# Qwiic_KX13X.net
KiCad netlist of a schematic drawn in EAGLE
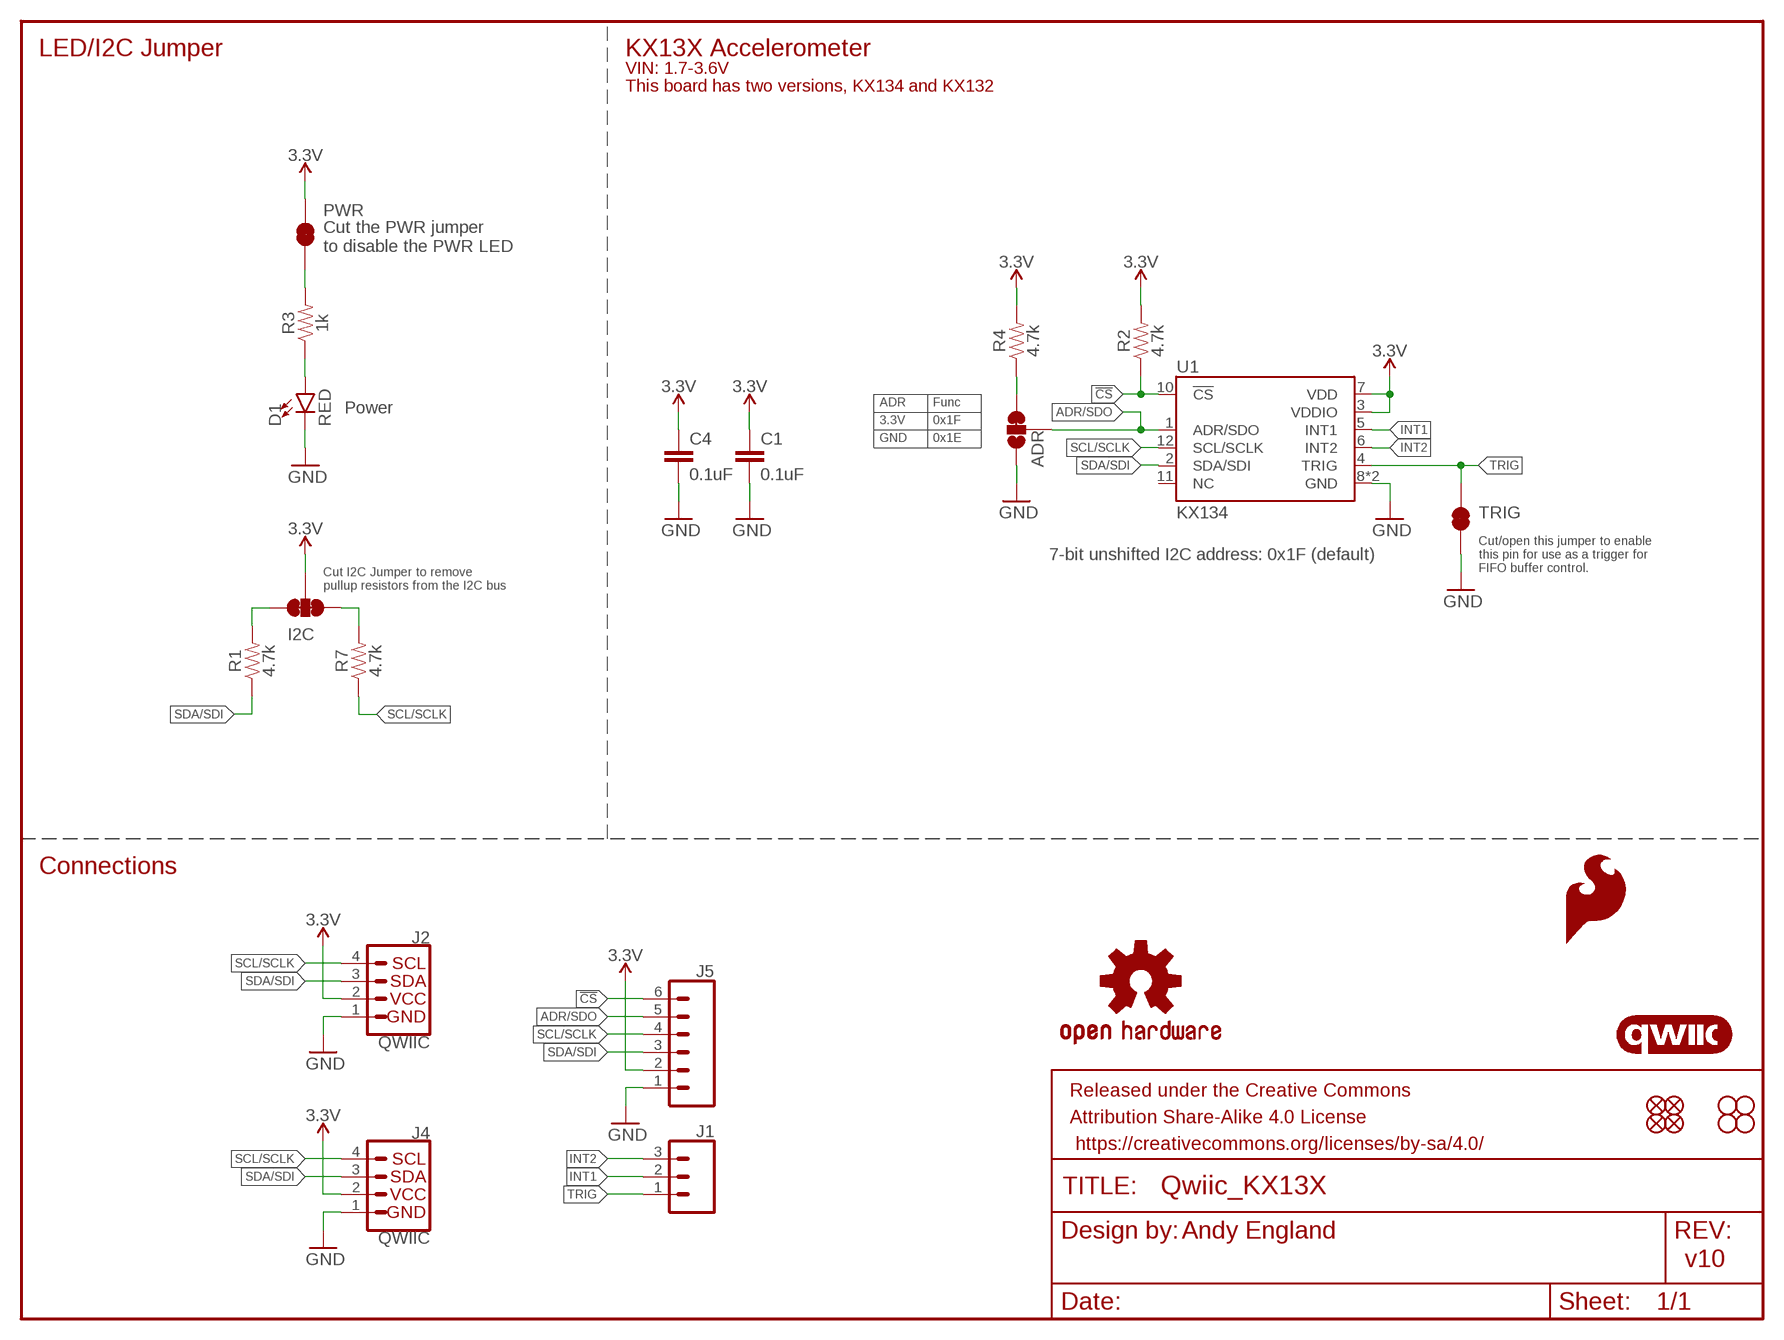
[diagram p0: schematic, sheet 1]

(export (version "E")
  (design (tool "Eeschema 10.0.6"))
  (components
    (comp (ref "ADR")
      (value "JUMPER-SMT_3_1-NC_TRACE_SILK")
      (footprint "eagle-import:SMT-JUMPER_3_1-NC_TRACE_SILK")
      (libsource (lib "eagle-import") (part "JUMPER-SMT_3_1-NC_TRACE_SILK"))
    )
    (comp (ref "C1")
      (value "0.1uF")
      (footprint "eagle-import:0603")
      (libsource (lib "eagle-import") (part "0.1UF-0603-25V-(+80/-20%)"))
    )
    (comp (ref "C4")
      (value "0.1uF")
      (footprint "eagle-import:0603")
      (libsource (lib "eagle-import") (part "0.1UF-0603-25V-(+80/-20%)"))
    )
    (comp (ref "D1")
      (value "RED")
      (footprint "eagle-import:LED-0603")
      (libsource (lib "eagle-import") (part "LED-RED0603"))
    )
    (comp (ref "FRAME1")
      (value "FRAME-LETTER")
      (footprint "eagle-import:CREATIVE_COMMONS")
      (libsource (lib "eagle-import") (part "FRAME-LETTER"))
    )
    (comp (ref "I2C")
      (value "JUMPER-SMT_3_2-NC_TRACE_SILK")
      (footprint "eagle-import:SMT-JUMPER_3_2-NC_TRACE_SILK")
      (libsource (lib "eagle-import") (part "JUMPER-SMT_3_2-NC_TRACE_SILK"))
    )
    (comp (ref "J1")
      (value "CONN_031X03_NO_SILK")
      (footprint "eagle-import:1X03_NO_SILK")
      (libsource (lib "eagle-import") (part "CONN_031X03_NO_SILK"))
    )
    (comp (ref "J2")
      (value "QWIIC")
      (footprint "eagle-import:JST04_1MM_RA")
      (libsource (lib "eagle-import") (part "QWIIC_CONNECTORJS-1MM"))
    )
    (comp (ref "J4")
      (value "QWIIC")
      (footprint "eagle-import:JST04_1MM_RA")
      (libsource (lib "eagle-import") (part "QWIIC_CONNECTORJS-1MM"))
    )
    (comp (ref "J5")
      (value "CONN_06NO_SILK_NO_POP")
      (footprint "eagle-import:1X06_NO_SILK")
      (libsource (lib "eagle-import") (part "CONN_06NO_SILK_NO_POP"))
    )
    (comp (ref "JP1")
      (value "FIDUCIALUFIDUCIAL")
      (footprint "eagle-import:MICRO-FIDUCIAL")
      (libsource (lib "eagle-import") (part "FIDUCIALUFIDUCIAL"))
    )
    (comp (ref "JP2")
      (value "FIDUCIALUFIDUCIAL")
      (footprint "eagle-import:MICRO-FIDUCIAL")
      (libsource (lib "eagle-import") (part "FIDUCIALUFIDUCIAL"))
    )
    (comp (ref "JP3")
      (value "STAND-OFF")
      (footprint "eagle-import:STAND-OFF")
      (libsource (lib "eagle-import") (part "STAND-OFF"))
    )
    (comp (ref "JP4")
      (value "STAND-OFF")
      (footprint "eagle-import:STAND-OFF")
      (libsource (lib "eagle-import") (part "STAND-OFF"))
    )
    (comp (ref "JP5")
      (value "FIDUCIALUFIDUCIAL")
      (footprint "eagle-import:MICRO-FIDUCIAL")
      (libsource (lib "eagle-import") (part "FIDUCIALUFIDUCIAL"))
    )
    (comp (ref "JP6")
      (value "FIDUCIALUFIDUCIAL")
      (footprint "eagle-import:MICRO-FIDUCIAL")
      (libsource (lib "eagle-import") (part "FIDUCIALUFIDUCIAL"))
    )
    (comp (ref "JP7")
      (value "STAND-OFF")
      (footprint "eagle-import:STAND-OFF")
      (libsource (lib "eagle-import") (part "STAND-OFF"))
    )
    (comp (ref "JP8")
      (value "STAND-OFF")
      (footprint "eagle-import:STAND-OFF")
      (libsource (lib "eagle-import") (part "STAND-OFF"))
    )
    (comp (ref "LOGO1")
      (value "SFE_LOGO_FLAME.1_INCH")
      (footprint "eagle-import:SFE_LOGO_FLAME_.1")
      (libsource (lib "eagle-import") (part "SFE_LOGO_FLAME.1_INCH"))
    )
    (comp (ref "LOGO2")
      (value "SFE_LOGO_FLAME.1_INCH")
      (footprint "eagle-import:SFE_LOGO_FLAME_.1")
      (libsource (lib "eagle-import") (part "SFE_LOGO_FLAME.1_INCH"))
    )
    (comp (ref "LOGO3")
      (value "QWIIC_LOGO_4MM")
      (footprint "eagle-import:QWIIC_4MM")
      (libsource (lib "eagle-import") (part "QWIIC_LOGO_4MM"))
    )
    (comp (ref "LOGO5")
      (value "OSHW-LOGOS")
      (footprint "eagle-import:OSHW-LOGO-S")
      (libsource (lib "eagle-import") (part "OSHW-LOGOS"))
    )
    (comp (ref "PWR")
      (value "JUMPER-SMT_2_NC_TRACE_SILK")
      (footprint "eagle-import:SMT-JUMPER_2_NC_TRACE_SILK")
      (libsource (lib "eagle-import") (part "JUMPER-SMT_2_NC_TRACE_SILK"))
    )
    (comp (ref "R1")
      (value "4.7k")
      (footprint "eagle-import:0603")
      (libsource (lib "eagle-import") (part "4.7KOHM-0603-1/10W-1%"))
    )
    (comp (ref "R2")
      (value "4.7k")
      (footprint "eagle-import:0603")
      (libsource (lib "eagle-import") (part "4.7KOHM-0603-1/10W-1%"))
    )
    (comp (ref "R3")
      (value "1k")
      (footprint "eagle-import:0603")
      (libsource (lib "eagle-import") (part "1KOHM-0603-1/10W-1%"))
    )
    (comp (ref "R4")
      (value "4.7k")
      (footprint "eagle-import:0603")
      (libsource (lib "eagle-import") (part "4.7KOHM-0603-1/10W-1%"))
    )
    (comp (ref "R7")
      (value "4.7k")
      (footprint "eagle-import:0603")
      (libsource (lib "eagle-import") (part "4.7KOHM-0603-1/10W-1%"))
    )
    (comp (ref "TRIG")
      (value "JUMPER-SMT_2_NC_TRACE_SILK")
      (footprint "eagle-import:SMT-JUMPER_2_NC_TRACE_SILK")
      (libsource (lib "eagle-import") (part "JUMPER-SMT_2_NC_TRACE_SILK"))
    )
    (comp (ref "U1")
      (value "KX134")
      (footprint "eagle-import:KX13X")
      (libsource (lib "eagle-import") (part "KX13X-KX134"))
    )
  )
  (nets
    (net (code "1") (name "/~{CS}") (class "Default")
      (node (ref "J5") (pin "6") (pinfunction "6_6") (pintype "passive"))
      (node (ref "R2") (pin "1") (pinfunction "1_1") (pintype "passive"))
      (node (ref "U1") (pin "10") (pinfunction "~{CS}_10") (pintype "bidirectional"))
    )
    (net (code "2") (name "3.3V") (class "Default")
      (node (ref "C1") (pin "1") (pinfunction "1_1") (pintype "passive"))
      (node (ref "C4") (pin "1") (pinfunction "1_1") (pintype "passive"))
      (node (ref "I2C") (pin "2") (pinfunction "2_2") (pintype "passive"))
      (node (ref "J2") (pin "2") (pinfunction "2_2") (pintype "power_in"))
      (node (ref "J4") (pin "2") (pinfunction "2_2") (pintype "power_in"))
      (node (ref "J5") (pin "2") (pinfunction "2_2") (pintype "passive"))
      (node (ref "PWR") (pin "2") (pinfunction "2_2") (pintype "passive"))
      (node (ref "R2") (pin "2") (pinfunction "2_2") (pintype "passive"))
      (node (ref "R4") (pin "2") (pinfunction "2_2") (pintype "passive"))
      (node (ref "U1") (pin "3") (pinfunction "VDDIO_3") (pintype "bidirectional"))
      (node (ref "U1") (pin "7") (pinfunction "VDD_7") (pintype "bidirectional"))
    )
    (net (code "3") (name "ADR{slash}SDO") (class "Default")
      (node (ref "ADR") (pin "2") (pinfunction "2_2") (pintype "passive"))
      (node (ref "J5") (pin "5") (pinfunction "5_5") (pintype "passive"))
      (node (ref "U1") (pin "1") (pinfunction "ADR/SDO_1") (pintype "bidirectional"))
    )
    (net (code "4") (name "GND") (class "Default")
      (node (ref "ADR") (pin "1") (pinfunction "1_1") (pintype "passive"))
      (node (ref "C1") (pin "2") (pinfunction "2_2") (pintype "passive"))
      (node (ref "C4") (pin "2") (pinfunction "2_2") (pintype "passive"))
      (node (ref "D1") (pin "C") (pinfunction "C_C") (pintype "passive"))
      (node (ref "J2") (pin "1") (pinfunction "1_1") (pintype "power_in"))
      (node (ref "J4") (pin "1") (pinfunction "1_1") (pintype "power_in"))
      (node (ref "J5") (pin "1") (pinfunction "1_1") (pintype "passive"))
      (node (ref "TRIG") (pin "2") (pinfunction "2_2") (pintype "passive"))
      (node (ref "U1") (pin "8") (pinfunction "GND_8") (pintype "bidirectional"))
      (node (ref "U1") (pin "9") (pinfunction "GND_9") (pintype "bidirectional"))
    )
    (net (code "5") (name "INT1") (class "Default")
      (node (ref "J1") (pin "2") (pinfunction "2_2") (pintype "passive"))
      (node (ref "U1") (pin "5") (pinfunction "INT1_5") (pintype "bidirectional"))
    )
    (net (code "6") (name "INT2") (class "Default")
      (node (ref "J1") (pin "3") (pinfunction "3_3") (pintype "passive"))
      (node (ref "U1") (pin "6") (pinfunction "INT2_6") (pintype "bidirectional"))
    )
    (net (code "7") (name "Net-(ADR-Pad3)") (class "Default")
      (node (ref "ADR") (pin "3") (pinfunction "3_3") (pintype "passive"))
      (node (ref "R4") (pin "1") (pinfunction "1_1") (pintype "passive"))
    )
    (net (code "8") (name "Net-(D1-PadA)") (class "Default")
      (node (ref "D1") (pin "A") (pinfunction "A_A") (pintype "passive"))
      (node (ref "R3") (pin "1") (pinfunction "1_1") (pintype "passive"))
    )
    (net (code "9") (name "Net-(I2C-Pad1)") (class "Default")
      (node (ref "I2C") (pin "1") (pinfunction "1_1") (pintype "passive"))
      (node (ref "R7") (pin "2") (pinfunction "2_2") (pintype "passive"))
    )
    (net (code "10") (name "Net-(I2C-Pad3)") (class "Default")
      (node (ref "I2C") (pin "3") (pinfunction "3_3") (pintype "passive"))
      (node (ref "R1") (pin "2") (pinfunction "2_2") (pintype "passive"))
    )
    (net (code "11") (name "Net-(PWR-Pad1)") (class "Default")
      (node (ref "PWR") (pin "1") (pinfunction "1_1") (pintype "passive"))
      (node (ref "R3") (pin "2") (pinfunction "2_2") (pintype "passive"))
    )
    (net (code "12") (name "SCL{slash}SCLK") (class "Default")
      (node (ref "J2") (pin "4") (pinfunction "4_4") (pintype "passive"))
      (node (ref "J4") (pin "4") (pinfunction "4_4") (pintype "passive"))
      (node (ref "J5") (pin "4") (pinfunction "4_4") (pintype "passive"))
      (node (ref "R7") (pin "1") (pinfunction "1_1") (pintype "passive"))
      (node (ref "U1") (pin "12") (pinfunction "SCL/SCLK_12") (pintype "bidirectional"))
    )
    (net (code "13") (name "SDA{slash}SDI") (class "Default")
      (node (ref "J2") (pin "3") (pinfunction "3_3") (pintype "passive"))
      (node (ref "J4") (pin "3") (pinfunction "3_3") (pintype "passive"))
      (node (ref "J5") (pin "3") (pinfunction "3_3") (pintype "passive"))
      (node (ref "R1") (pin "1") (pinfunction "1_1") (pintype "passive"))
      (node (ref "U1") (pin "2") (pinfunction "SDA/SDI_2") (pintype "bidirectional"))
    )
    (net (code "14") (name "TRIG") (class "Default")
      (node (ref "J1") (pin "1") (pinfunction "1_1") (pintype "passive"))
      (node (ref "TRIG") (pin "1") (pinfunction "1_1") (pintype "passive"))
      (node (ref "U1") (pin "4") (pinfunction "TRIG_4") (pintype "bidirectional"))
    )
    (net (code "15") (name "unconnected-(U1-NC-Pad11)") (class "Default")
      (node (ref "U1") (pin "11") (pinfunction "NC_11") (pintype "no_connect"))
    )
  )
)
